# FABLAB_BOT_00.net
KiCad netlist of a schematic drawn in Altium Designer
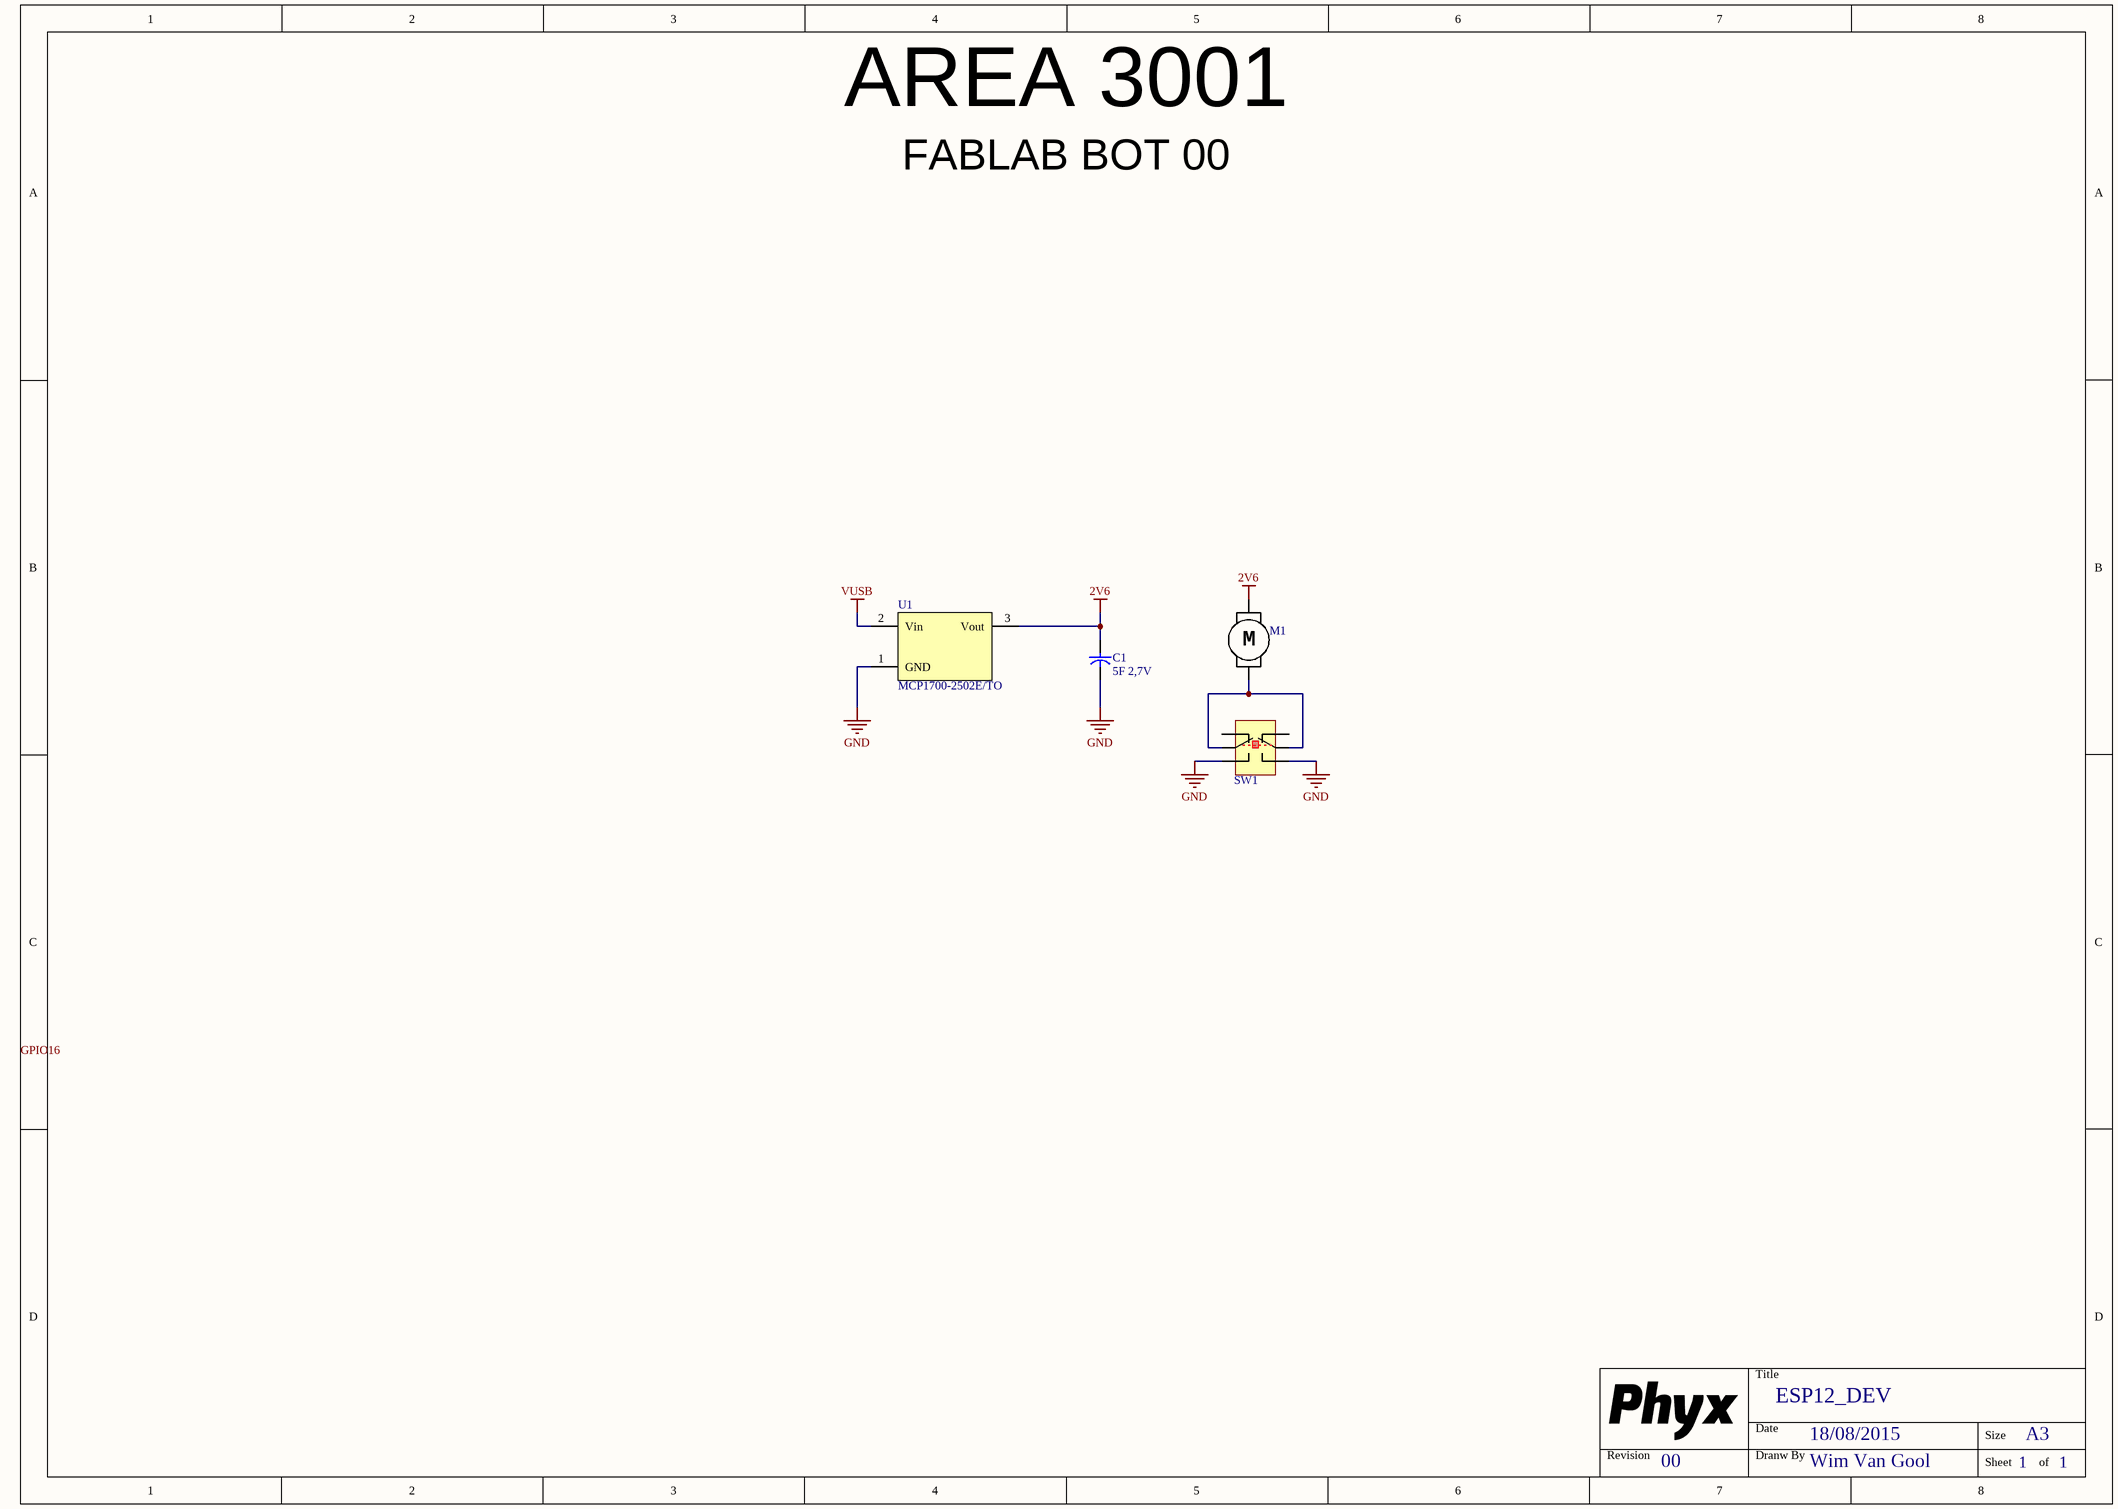
[diagram p0: FABLAB_BOT_00.SchDoc]

(export (version "E")
  (design (tool "Eeschema 10.0.6"))
  (components
    (comp (ref "C1")
      (value "5F 2,7V")
      (footprint "C_10x20mm")
      (description "Capacitor electrolyt")
      (fields (field (name "Comment") "CAP_POL"))
      (libsource (lib "Phyx_Components") (part "CAP_POL"))
    )
    (comp (ref "M1")
      (value "Vibration Motor 3,9 x 8,5mm")
      (footprint "VBR_3.9x8.5")
      (description "=Description")
      (libsource (lib "Phyx_Components") (part "MOTOR"))
    )
    (comp (ref "SW1")
      (value "mini Switch 2 pole double throw")
      (footprint "MCLSS22P")
      (libsource (lib "Phyx_Components") (part "SW_2P2T"))
    )
    (comp (ref "U1")
      (value "MCP1700-2502E/TO")
      (footprint "TO-92A")
      (description "=Designator")
      (fields (field (name "Comment") "2,5V LDO"))
      (libsource (lib "Phyx_Components") (part "MCP1700-TO"))
    )
  )
  (nets
    (net (code "2") (name "2V6") (class "Default")
      (node (ref "C1") (pin "1") (pinfunction "1_1") (pintype "passive"))
      (node (ref "M1") (pin "1") (pinfunction "1_1") (pintype "passive"))
      (node (ref "U1") (pin "3") (pinfunction "Vout_3") (pintype "power_in"))
    )
    (net (code "3") (name "GND") (class "Default")
      (node (ref "C1") (pin "2") (pinfunction "2_2") (pintype "passive"))
      (node (ref "SW1") (pin "5") (pinfunction "5_5") (pintype "passive"))
      (node (ref "SW1") (pin "6") (pinfunction "5_6") (pintype "passive"))
      (node (ref "U1") (pin "1") (pinfunction "GND_1") (pintype "power_in"))
    )
    (net (code "4") (name "Net-(M1-Pad2)") (class "Default")
      (node (ref "M1") (pin "2") (pinfunction "2_2") (pintype "passive"))
      (node (ref "SW1") (pin "3") (pinfunction "3_3") (pintype "passive"))
      (node (ref "SW1") (pin "4") (pinfunction "4_4") (pintype "passive"))
    )
    (net (code "5") (name "VUSB") (class "Default")
      (node (ref "U1") (pin "2") (pinfunction "Vin_2") (pintype "power_in"))
    )
    (net (code "6") (name "unconnected-(SW1-Pad1)") (class "Default")
      (node (ref "SW1") (pin "1") (pinfunction "1_1") (pintype "passive"))
    )
    (net (code "7") (name "unconnected-(SW1-Pad2)") (class "Default")
      (node (ref "SW1") (pin "2") (pinfunction "2_2") (pintype "passive"))
    )
  )
)
